# CurrenSens.net
KiCad netlist of a schematic drawn in Altium Designer
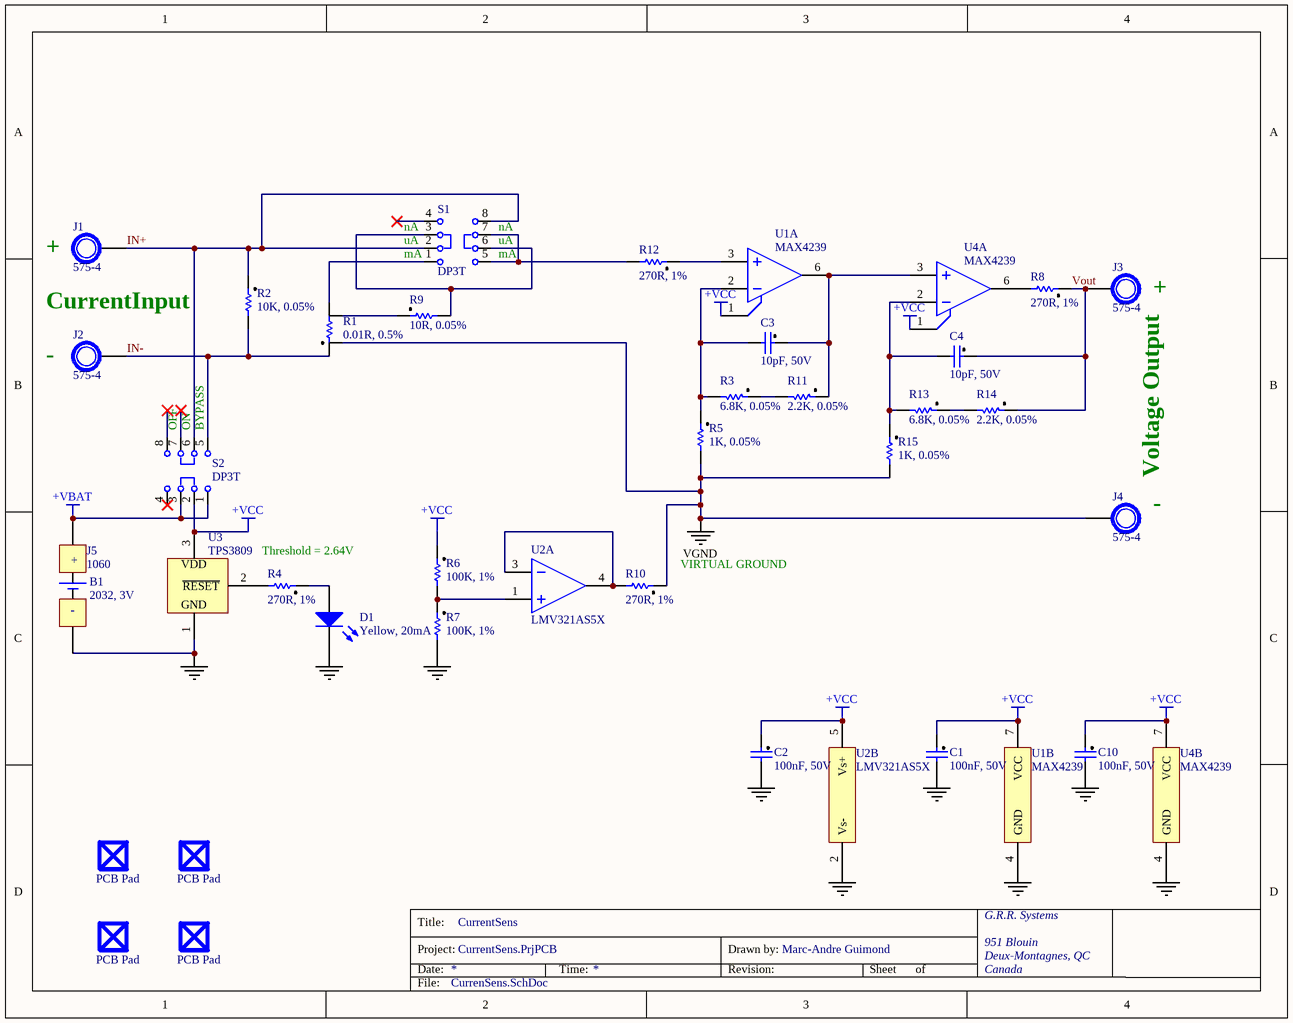
[diagram p0: CurrenSens.SchDoc]

(export (version "E")
  (design (tool "Eeschema 10.0.6"))
  (components
    (comp (ref "B1")
      (value "2032, 3V")
      (footprint "NO_FOOT")
      (description "BATTERY LITHIUM COIN 3V 20MM")
      (fields
        (field (name "MANUFACTURER") "Panasonic - BSG")
        (field (name "MANUFACTURER PART NUMBER") "CR2032")
      )
      (libsource (lib "GRR_RnD") (part "CR2032"))
    )
    (comp (ref "C1")
      (value "100nF, 50V")
      (footprint "0603 (1608 Metric)")
      (description "CAP CER 100NF 50V 10% X7R 0603")
      (fields
        (field (name "MANUFACTURER") "Samsung Electro-Mechanics America, Inc")
        (field (name "MANUFACTURER PART NUMBER") "CL10B104KB8SFNC")
      )
      (libsource (lib "GRR_RnD") (part "CL10B104KB8SFNC"))
    )
    (comp (ref "C2")
      (value "100nF, 50V")
      (footprint "0603 (1608 Metric)")
      (description "CAP CER 100NF 50V 10% X7R 0603")
      (fields
        (field (name "MANUFACTURER") "Samsung Electro-Mechanics America, Inc")
        (field (name "MANUFACTURER PART NUMBER") "CL10B104KB8SFNC")
      )
      (libsource (lib "GRR_RnD") (part "CL10B104KB8SFNC"))
    )
    (comp (ref "C3")
      (value "10pF, 50V")
      (footprint "0603 (1608 Metric)")
      (description "CAP CER 10PF 50V 5% NP0 0603")
      (fields
        (field (name "MANUFACTURER") "Samsung Electro-Mechanics America, Inc")
        (field (name "MANUFACTURER PART NUMBER") "CL10C100JB8NCNC")
      )
      (libsource (lib "GRR_RnD") (part "CL10C100JB8NCNC"))
    )
    (comp (ref "C4")
      (value "10pF, 50V")
      (footprint "0603 (1608 Metric)")
      (description "CAP CER 10PF 50V 5% NP0 0603")
      (fields
        (field (name "MANUFACTURER") "Samsung Electro-Mechanics America, Inc")
        (field (name "MANUFACTURER PART NUMBER") "CL10C100JB8NCNC")
      )
      (libsource (lib "GRR_RnD") (part "CL10C100JB8NCNC"))
    )
    (comp (ref "C10")
      (value "100nF, 50V")
      (footprint "0603 (1608 Metric)")
      (description "CAP CER 100NF 50V 10% X7R 0603")
      (fields
        (field (name "MANUFACTURER") "Samsung Electro-Mechanics America, Inc")
        (field (name "MANUFACTURER PART NUMBER") "CL10B104KB8SFNC")
      )
      (libsource (lib "GRR_RnD") (part "CL10B104KB8SFNC"))
    )
    (comp (ref "D1")
      (value "Yellow, 20mA")
      (footprint "GRR_Footprints:1206 (3216 Metric)")
      (description "LED 3.2X1.6MM 590NM YLW CLR SMD")
      (fields
        (field (name "MANUFACTURER") "Kingbright")
        (field (name "MANUFACTURER PART NUMBER") "APTR3216SYCK")
      )
      (libsource (lib "GRR_LED") (part "APTR3216SYCK"))
    )
    (comp (ref "H1")
      (value "PCB Pad")
      (footprint "GRR_Footprints:SJ-5518")
      (description "BUMPER SQUARE 0.5\"L X 0.5\"W BLK")
      (fields (field (name "MANUFACTURER") "3M") (field (name "MANUFACTURER PART NUMBER") "SJ-5518 (BLACK)"))
      (libsource (lib "GRR_Hardware") (part "SJ-5518 (BLACK)"))
    )
    (comp (ref "H2")
      (value "PCB Pad")
      (footprint "GRR_Footprints:SJ-5518")
      (description "BUMPER SQUARE 0.5\"L X 0.5\"W BLK")
      (fields (field (name "MANUFACTURER") "3M") (field (name "MANUFACTURER PART NUMBER") "SJ-5518 (BLACK)"))
      (libsource (lib "GRR_Hardware") (part "SJ-5518 (BLACK)"))
    )
    (comp (ref "H3")
      (value "PCB Pad")
      (footprint "GRR_Footprints:SJ-5518")
      (description "BUMPER SQUARE 0.5\"L X 0.5\"W BLK")
      (fields (field (name "MANUFACTURER") "3M") (field (name "MANUFACTURER PART NUMBER") "SJ-5518 (BLACK)"))
      (libsource (lib "GRR_Hardware") (part "SJ-5518 (BLACK)"))
    )
    (comp (ref "H4")
      (value "PCB Pad")
      (footprint "GRR_Footprints:SJ-5518")
      (description "BUMPER SQUARE 0.5\"L X 0.5\"W BLK")
      (fields (field (name "MANUFACTURER") "3M") (field (name "MANUFACTURER PART NUMBER") "SJ-5518 (BLACK)"))
      (libsource (lib "GRR_Hardware") (part "SJ-5518 (BLACK)"))
    )
    (comp (ref "J1")
      (value "575-4")
      (footprint "CON_BANANA_TH_NI")
      (description "JACK NON-INSULATED .218\"")
      (fields (field (name "MANUFACTURER") "Keystone Electronics"))
      (libsource (lib "GRR_RnD") (part "575-4"))
    )
    (comp (ref "J2")
      (value "575-4")
      (footprint "CON_BANANA_TH_NI")
      (description "JACK NON-INSULATED .218\"")
      (fields (field (name "MANUFACTURER") "Keystone Electronics"))
      (libsource (lib "GRR_RnD") (part "575-4"))
    )
    (comp (ref "J3")
      (value "575-4")
      (footprint "CON_BANANA_TH_NI")
      (description "JACK NON-INSULATED .218\"")
      (fields (field (name "MANUFACTURER") "Keystone Electronics"))
      (libsource (lib "GRR_RnD") (part "575-4"))
    )
    (comp (ref "J4")
      (value "575-4")
      (footprint "CON_BANANA_TH_NI")
      (description "JACK NON-INSULATED .218\"")
      (fields (field (name "MANUFACTURER") "Keystone Electronics"))
      (libsource (lib "GRR_RnD") (part "575-4"))
    )
    (comp (ref "J5")
      (value "1060")
      (footprint "1060")
      (description "HOLDER BATT COIN 2032 20MM SMD")
      (fields (field (name "MANUFACTURER") "Keystone Electronics"))
      (libsource (lib "GRR_RnD") (part "1060"))
    )
    (comp (ref "R1")
      (value "0.01R, 0.5%")
      (footprint "2512 (6432 Metric)")
      (description "RES 0.01 OHM 1W 0.5% 2412")
      (fields (field (name "MANUFACTURER") "Ohmite") (field (name "MANUFACTURER PART NUMBER") "LVK24R010DER"))
      (libsource (lib "GRR_RnD") (part "LVK24R010DER"))
    )
    (comp (ref "R2")
      (value "10K, 0.05%")
      (footprint "0603 (1608 Metric)")
      (description "RES 10.0K OHM 1/10W .05% 0603SMD")
      (fields
        (field (name "MANUFACTURER") "Susumu")
        (field (name "MANUFACTURER PART NUMBER") "RG1608N-103-W-T1")
      )
      (libsource (lib "GRR_RnD") (part "RG1608N-103-W-T1"))
    )
    (comp (ref "R3")
      (value "6.8K, 0.05%")
      (footprint "0603 (1608 Metric)")
      (description "RES 6.8K OHM 1/10W .05% 0603 SMD")
      (fields
        (field (name "MANUFACTURER") "Susumu")
        (field (name "MANUFACTURER PART NUMBER") "RG1608N-682-W-T1")
      )
      (libsource (lib "GRR_RnD") (part "RG1608N-682-W-T1"))
    )
    (comp (ref "R4")
      (value "270R, 1%")
      (footprint "0603 (1608 Metric)")
      (description "RES 270 OHM 1/8W 1% 0805")
      (fields
        (field (name "MANUFACTURER") "Stackpole Electronics Inc")
        (field (name "MANUFACTURER PART NUMBER") "RMCF0805FT270R")
      )
      (libsource (lib "GRR_RnD") (part "RMCF0805FT270R"))
    )
    (comp (ref "R5")
      (value "1K, 0.05%")
      (footprint "0603 (1608 Metric)")
      (description "RES 1K OHM 1/10W .05% 0603 SMD")
      (fields
        (field (name "MANUFACTURER") "Susumu")
        (field (name "MANUFACTURER PART NUMBER") "RG1608N-102-W-T1")
      )
      (libsource (lib "GRR_RnD") (part "RG1608N-102-W-T1"))
    )
    (comp (ref "R6")
      (value "100K, 1%")
      (footprint "0603 (1608 Metric)")
      (description "RES 100K OHM 1/8W 1% SMD 0603")
      (fields
        (field (name "MANUFACTURER") "Vishay Beyschlag")
        (field (name "MANUFACTURER PART NUMBER") "MCT06030C1003FP500")
      )
      (libsource (lib "GRR_RnD") (part "MCT06030C1003FP500"))
    )
    (comp (ref "R7")
      (value "100K, 1%")
      (footprint "0603 (1608 Metric)")
      (description "RES 100K OHM 1/8W 1% SMD 0603")
      (fields
        (field (name "MANUFACTURER") "Vishay Beyschlag")
        (field (name "MANUFACTURER PART NUMBER") "MCT06030C1003FP500")
      )
      (libsource (lib "GRR_RnD") (part "MCT06030C1003FP500"))
    )
    (comp (ref "R8")
      (value "270R, 1%")
      (footprint "0603 (1608 Metric)")
      (description "RES 270 OHM 1/8W 1% 0805")
      (fields
        (field (name "MANUFACTURER") "Stackpole Electronics Inc")
        (field (name "MANUFACTURER PART NUMBER") "RMCF0805FT270R")
      )
      (libsource (lib "GRR_RnD") (part "RMCF0805FT270R"))
    )
    (comp (ref "R9")
      (value "10R, 0.05%")
      (footprint "0805 (2012 Metric)")
      (description "RES 10 OHM 1/10W 0.05% 0805")
      (fields
        (field (name "MANUFACTURER") "Stackpole Electronics Inc")
        (field (name "MANUFACTURER PART NUMBER") "RNCF0805AKT10R0")
      )
      (libsource (lib "GRR_RnD") (part "RNCF0805AKT10R0"))
    )
    (comp (ref "R10")
      (value "270R, 1%")
      (footprint "0603 (1608 Metric)")
      (description "RES 270 OHM 1/8W 1% 0805")
      (fields
        (field (name "MANUFACTURER") "Stackpole Electronics Inc")
        (field (name "MANUFACTURER PART NUMBER") "RMCF0805FT270R")
      )
      (libsource (lib "GRR_RnD") (part "RMCF0805FT270R"))
    )
    (comp (ref "R11")
      (value "2.2K, 0.05%")
      (footprint "GRR_Footprints:0603 (1608 Metric)")
      (description "RES 2.2K OHM 1/10W .05% 0603 SMD")
      (fields
        (field (name "MANUFACTURER") "Susumu")
        (field (name "MANUFACTURER PART NUMBER") "RG1608N-222-W-T1")
      )
      (libsource (lib "GRR_Resistor") (part "RG1608N-222-W-T1"))
    )
    (comp (ref "R12")
      (value "270R, 1%")
      (footprint "0603 (1608 Metric)")
      (description "RES 270 OHM 1/8W 1% 0805")
      (fields
        (field (name "MANUFACTURER") "Stackpole Electronics Inc")
        (field (name "MANUFACTURER PART NUMBER") "RMCF0805FT270R")
      )
      (libsource (lib "GRR_RnD") (part "RMCF0805FT270R"))
    )
    (comp (ref "R13")
      (value "6.8K, 0.05%")
      (footprint "0603 (1608 Metric)")
      (description "RES 6.8K OHM 1/10W .05% 0603 SMD")
      (fields
        (field (name "MANUFACTURER") "Susumu")
        (field (name "MANUFACTURER PART NUMBER") "RG1608N-682-W-T1")
      )
      (libsource (lib "GRR_RnD") (part "RG1608N-682-W-T1"))
    )
    (comp (ref "R14")
      (value "2.2K, 0.05%")
      (footprint "GRR_Footprints:0603 (1608 Metric)")
      (description "RES 2.2K OHM 1/10W .05% 0603 SMD")
      (fields
        (field (name "MANUFACTURER") "Susumu")
        (field (name "MANUFACTURER PART NUMBER") "RG1608N-222-W-T1")
      )
      (libsource (lib "GRR_Resistor") (part "RG1608N-222-W-T1"))
    )
    (comp (ref "R15")
      (value "1K, 0.05%")
      (footprint "0603 (1608 Metric)")
      (description "RES 1K OHM 1/10W .05% 0603 SMD")
      (fields
        (field (name "MANUFACTURER") "Susumu")
        (field (name "MANUFACTURER PART NUMBER") "RG1608N-102-W-T1")
      )
      (libsource (lib "GRR_RnD") (part "RG1608N-102-W-T1"))
    )
    (comp (ref "S1")
      (value "DP3T")
      (footprint "L203-MS")
      (description "SWITCH SLIDE DP3T 4A PC 125V")
      (fields
        (field (name "MANUFACTURER") "C&K Components")
        (field (name "MANUFACTURER PART NUMBER") "L203011MS02Q")
      )
      (libsource (lib "GRR_RnD") (part "L203011MS02Q"))
    )
    (comp (ref "S2")
      (value "DP3T")
      (footprint "L203-MS")
      (description "SWITCH SLIDE DP3T 4A PC 125V")
      (fields
        (field (name "MANUFACTURER") "C&K Components")
        (field (name "MANUFACTURER PART NUMBER") "L203011MS02Q")
      )
      (libsource (lib "GRR_RnD") (part "L203011MS02Q"))
    )
    (comp (ref "U1")
      (value "MAX4239")
      (footprint "GRR_Footprints:SOIC8_154MIL")
      (description "IC OPAMP GP 6.5MHZ RRO 8SOIC")
      (fields
        (field (name "MANUFACTURER") "Maxim Integrated")
        (field (name "MANUFACTURER PART NUMBER") "MAX4239ASA+")
      )
      (libsource (lib "") (part "MAX4239ASA+-ND_1"))
    )
    (comp (ref "U2")
      (value "LMV321AS5X")
      (footprint "SOT23-5")
      (description "IC OPAMP VFB 1.4MHZ RRO SOT23-5")
      (fields (field (name "MANUFACTURER") "Fairchild Semiconductor"))
      (libsource (lib "GRR_RnD") (part "LMV321AS5X"))
    )
    (comp (ref "U3")
      (value "TPS3809")
      (footprint "SOT23-3")
      (description "IC 2.64V SUPPLY MONITOR SOT-23-3")
      (fields
        (field (name "MANUFACTURER") "Texas Instruments")
        (field (name "MANUFACTURER PART NUMBER") "TPS3809L30DBVR")
      )
      (libsource (lib "GRR_RnD") (part "TPS3809L30DBVR"))
    )
    (comp (ref "U4")
      (value "MAX4239")
      (footprint "GRR_Footprints:SOIC8_154MIL")
      (description "IC OPAMP GP 6.5MHZ RRO 8SOIC")
      (fields
        (field (name "MANUFACTURER") "Maxim Integrated")
        (field (name "MANUFACTURER PART NUMBER") "MAX4239ASA+")
      )
      (libsource (lib "GRR_IC") (part "MAX4239ASA+-ND"))
    )
  )
  (nets
    (net (code "1") (name "+VBAT") (class "Default")
      (node (ref "J5") (pin "1") (pinfunction "1_1") (pintype "passive"))
      (node (ref "S2") (pin "1") (pinfunction "1_1") (pintype "passive"))
      (node (ref "S2") (pin "3") (pinfunction "3_3") (pintype "passive"))
    )
    (net (code "2") (name "+VCC") (class "Default")
      (node (ref "C1") (pin "1") (pinfunction "1_1") (pintype "passive"))
      (node (ref "C10") (pin "1") (pinfunction "1_1") (pintype "passive"))
      (node (ref "C2") (pin "1") (pinfunction "1_1") (pintype "passive"))
      (node (ref "R6") (pin "1") (pinfunction "1_1") (pintype "passive"))
      (node (ref "S2") (pin "2") (pinfunction "2_2") (pintype "passive"))
      (node (ref "U1") (pin "1") (pinfunction "~{SHDN}_1") (pintype "passive"))
      (node (ref "U1") (pin "7") (pinfunction "VCC_7") (pintype "power_in"))
      (node (ref "U2") (pin "5") (pinfunction "Vs+_5") (pintype "power_in"))
      (node (ref "U3") (pin "3") (pinfunction "VDD_3") (pintype "power_in"))
      (node (ref "U4") (pin "1") (pinfunction "~{SHDN}_1") (pintype "passive"))
      (node (ref "U4") (pin "7") (pinfunction "VCC_7") (pintype "power_in"))
    )
    (net (code "3") (name "/IN+") (class "Default")
      (node (ref "J1") (pin "1") (pinfunction "1_1") (pintype "passive"))
      (node (ref "R2") (pin "1") (pinfunction "1_1") (pintype "passive"))
      (node (ref "S1") (pin "2") (pinfunction "2_2") (pintype "passive"))
      (node (ref "S1") (pin "8") (pinfunction "8_8") (pintype "passive"))
      (node (ref "S2") (pin "6") (pinfunction "6_6") (pintype "passive"))
    )
    (net (code "4") (name "/IN-") (class "Default")
      (node (ref "J2") (pin "1") (pinfunction "1_1") (pintype "passive"))
      (node (ref "R1") (pin "1") (pinfunction "1_1") (pintype "passive"))
      (node (ref "R2") (pin "2") (pinfunction "2_2") (pintype "passive"))
      (node (ref "S2") (pin "5") (pinfunction "5_5") (pintype "passive"))
    )
    (net (code "5") (name "/Vout") (class "Default")
      (node (ref "C4") (pin "1") (pinfunction "1_1") (pintype "passive"))
      (node (ref "J3") (pin "1") (pinfunction "1_1") (pintype "passive"))
      (node (ref "R14") (pin "1") (pinfunction "1_1") (pintype "passive"))
      (node (ref "R8") (pin "1") (pinfunction "1_1") (pintype "passive"))
    )
    (net (code "6") (name "GND") (class "Default")
      (node (ref "C1") (pin "2") (pinfunction "2_2") (pintype "passive"))
      (node (ref "C10") (pin "2") (pinfunction "2_2") (pintype "passive"))
      (node (ref "C2") (pin "2") (pinfunction "2_2") (pintype "passive"))
      (node (ref "D1") (pin "2") (pinfunction "K_2") (pintype "passive"))
      (node (ref "J5") (pin "2") (pinfunction "2_2") (pintype "passive"))
      (node (ref "R7") (pin "2") (pinfunction "2_2") (pintype "passive"))
      (node (ref "U1") (pin "4") (pinfunction "GND_4") (pintype "power_in"))
      (node (ref "U2") (pin "2") (pinfunction "Vs-_2") (pintype "power_in"))
      (node (ref "U3") (pin "1") (pinfunction "GND_1") (pintype "power_in"))
      (node (ref "U4") (pin "4") (pinfunction "GND_4") (pintype "power_in"))
    )
    (net (code "7") (name "Net-(D1-A)") (class "Default")
      (node (ref "D1") (pin "1") (pinfunction "A_1") (pintype "passive"))
      (node (ref "R4") (pin "1") (pinfunction "1_1") (pintype "passive"))
    )
    (net (code "8") (name "Net-(R1-Pad2)") (class "Default")
      (node (ref "R1") (pin "2") (pinfunction "2_2") (pintype "passive"))
      (node (ref "S1") (pin "1") (pinfunction "1_1") (pintype "passive"))
    )
    (net (code "9") (name "Net-(R1-Pad4)") (class "Default")
      (node (ref "R1") (pin "4") (pinfunction "4_4") (pintype "passive"))
      (node (ref "R9") (pin "1") (pinfunction "1_1") (pintype "passive"))
    )
    (net (code "10") (name "Net-(R9-Pad2)") (class "Default")
      (node (ref "R9") (pin "2") (pinfunction "2_2") (pintype "passive"))
      (node (ref "S1") (pin "3") (pinfunction "3_3") (pintype "passive"))
      (node (ref "S1") (pin "6") (pinfunction "6_6") (pintype "passive"))
    )
    (net (code "11") (name "Net-(R11-Pad2)") (class "Default")
      (node (ref "R11") (pin "2") (pinfunction "2_2") (pintype "passive"))
      (node (ref "R3") (pin "1") (pinfunction "1_1") (pintype "passive"))
    )
    (net (code "12") (name "Net-(R12-Pad2)") (class "Default")
      (node (ref "R12") (pin "2") (pinfunction "2_2") (pintype "passive"))
      (node (ref "S1") (pin "5") (pinfunction "5_5") (pintype "passive"))
      (node (ref "S1") (pin "7") (pinfunction "7_7") (pintype "passive"))
    )
    (net (code "13") (name "Net-(R13-Pad1)") (class "Default")
      (node (ref "R13") (pin "1") (pinfunction "1_1") (pintype "passive"))
      (node (ref "R14") (pin "2") (pinfunction "2_2") (pintype "passive"))
    )
    (net (code "14") (name "Net-(U1A-IN+)") (class "Default")
      (node (ref "R12") (pin "1") (pinfunction "1_1") (pintype "passive"))
      (node (ref "U1") (pin "3") (pinfunction "IN+_3") (pintype "passive"))
    )
    (net (code "15") (name "Net-(U1A-IN-)") (class "Default")
      (node (ref "C3") (pin "2") (pinfunction "2_2") (pintype "passive"))
      (node (ref "R3") (pin "2") (pinfunction "2_2") (pintype "passive"))
      (node (ref "R5") (pin "1") (pinfunction "1_1") (pintype "passive"))
      (node (ref "U1") (pin "2") (pinfunction "IN-_2") (pintype "passive"))
    )
    (net (code "16") (name "Net-(U1A-OUT)") (class "Default")
      (node (ref "C3") (pin "1") (pinfunction "1_1") (pintype "passive"))
      (node (ref "R11") (pin "1") (pinfunction "1_1") (pintype "passive"))
      (node (ref "U1") (pin "6") (pinfunction "OUT_6") (pintype "passive"))
      (node (ref "U4") (pin "3") (pinfunction "IN+_3") (pintype "passive"))
    )
    (net (code "17") (name "Net-(U2A-IN+)") (class "Default")
      (node (ref "R6") (pin "2") (pinfunction "2_2") (pintype "passive"))
      (node (ref "R7") (pin "1") (pinfunction "1_1") (pintype "passive"))
      (node (ref "U2") (pin "1") (pinfunction "IN+_1") (pintype "passive"))
    )
    (net (code "18") (name "Net-(U2A-IN-)") (class "Default")
      (node (ref "R10") (pin "2") (pinfunction "2_2") (pintype "passive"))
      (node (ref "U2") (pin "3") (pinfunction "IN-_3") (pintype "passive"))
      (node (ref "U2") (pin "4") (pinfunction "OUT_4") (pintype "passive"))
    )
    (net (code "19") (name "Net-(U3-~{RESET})") (class "Default")
      (node (ref "R4") (pin "2") (pinfunction "2_2") (pintype "passive"))
      (node (ref "U3") (pin "2") (pinfunction "~{RESET}_2") (pintype "power_in"))
    )
    (net (code "20") (name "Net-(U4A-IN-)") (class "Default")
      (node (ref "C4") (pin "2") (pinfunction "2_2") (pintype "passive"))
      (node (ref "R13") (pin "2") (pinfunction "2_2") (pintype "passive"))
      (node (ref "R15") (pin "1") (pinfunction "1_1") (pintype "passive"))
      (node (ref "U4") (pin "2") (pinfunction "IN-_2") (pintype "passive"))
    )
    (net (code "21") (name "Net-(U4A-OUT)") (class "Default")
      (node (ref "R8") (pin "2") (pinfunction "2_2") (pintype "passive"))
      (node (ref "U4") (pin "6") (pinfunction "OUT_6") (pintype "passive"))
    )
    (net (code "22") (name "VGND") (class "Default")
      (node (ref "J4") (pin "1") (pinfunction "1_1") (pintype "passive"))
      (node (ref "R1") (pin "3") (pinfunction "3_3") (pintype "passive"))
      (node (ref "R10") (pin "1") (pinfunction "1_1") (pintype "passive"))
      (node (ref "R15") (pin "2") (pinfunction "2_2") (pintype "passive"))
      (node (ref "R5") (pin "2") (pinfunction "2_2") (pintype "passive"))
    )
    (net (code "23") (name "unconnected-(S1-Pad4)") (class "Default")
      (node (ref "S1") (pin "4") (pinfunction "4_4") (pintype "passive+no_connect"))
    )
    (net (code "24") (name "unconnected-(S2-Pad4)") (class "Default")
      (node (ref "S2") (pin "4") (pinfunction "4_4") (pintype "passive+no_connect"))
    )
    (net (code "25") (name "unconnected-(S2-Pad7)") (class "Default")
      (node (ref "S2") (pin "7") (pinfunction "7_7") (pintype "passive+no_connect"))
    )
    (net (code "26") (name "unconnected-(S2-Pad8)") (class "Default")
      (node (ref "S2") (pin "8") (pinfunction "8_8") (pintype "passive+no_connect"))
    )
    (net (code "27") (name "unconnected-(U1B-NC-Pad5)") (class "Default")
      (node (ref "U1") (pin "5") (pinfunction "NC_5") (pintype "passive"))
    )
    (net (code "28") (name "unconnected-(U1B-NC-Pad8)") (class "Default")
      (node (ref "U1") (pin "8") (pinfunction "NC_8") (pintype "passive"))
    )
    (net (code "29") (name "unconnected-(U4B-NC-Pad5)") (class "Default")
      (node (ref "U4") (pin "5") (pinfunction "NC_5") (pintype "passive"))
    )
    (net (code "30") (name "unconnected-(U4B-NC-Pad8)") (class "Default")
      (node (ref "U4") (pin "8") (pinfunction "NC_8") (pintype "passive"))
    )
  )
)
